# Fuzz-offboard.net
KiCad netlist of a schematic drawn in EAGLE
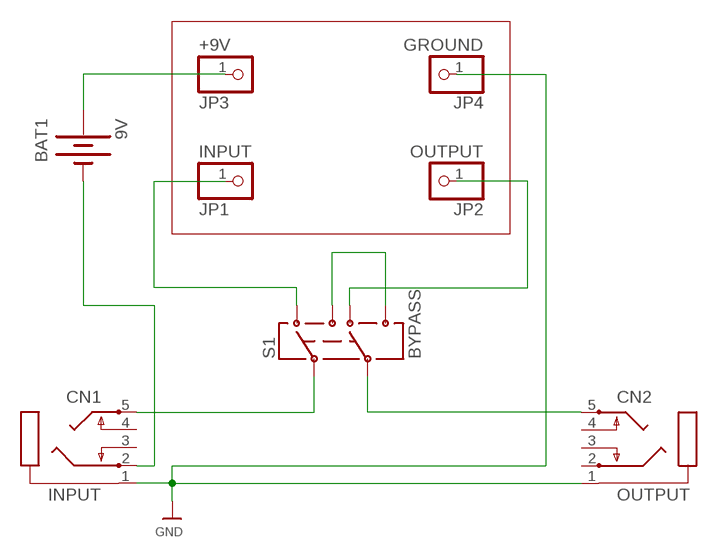
[diagram p0: schematic, sheet 1]

(export (version "E")
  (design (tool "Eeschema 10.0.6"))
  (components
    (comp (ref "BAT1")
      (value "9V")
      (footprint "eagle-import:BATTCON_9V")
      (libsource (lib "eagle-import") (part "BATTERY9V"))
    )
    (comp (ref "CN1")
      (value "INPUT")
      (footprint "eagle-import:STX3100")
      (libsource (lib "eagle-import") (part "AUDIO_STEREOJACK"))
    )
    (comp (ref "CN2")
      (value "OUTPUT")
      (footprint "eagle-import:STX3100")
      (libsource (lib "eagle-import") (part "AUDIO_STEREOJACK"))
    )
    (comp (ref "JP1")
      (value "INPUT")
      (footprint "eagle-import:1X01")
      (libsource (lib "eagle-import") (part "PINHD-1X1"))
    )
    (comp (ref "JP2")
      (value "OUTPUT")
      (footprint "eagle-import:1X01")
      (libsource (lib "eagle-import") (part "PINHD-1X1"))
    )
    (comp (ref "JP3")
      (value "+9V")
      (footprint "eagle-import:1X01")
      (libsource (lib "eagle-import") (part "PINHD-1X1"))
    )
    (comp (ref "JP4")
      (value "GROUND")
      (footprint "eagle-import:1X01")
      (libsource (lib "eagle-import") (part "PINHD-1X1"))
    )
    (comp (ref "S1")
      (value "BYPASS")
      (footprint "eagle-import:MS")
      (libsource (lib "eagle-import") (part "SWITCH-DPDTPTH1"))
    )
  )
  (nets
    (net (code "1") (name "GND") (class "Default")
      (node (ref "CN1") (pin "1") (pinfunction "1_1") (pintype "passive"))
      (node (ref "CN2") (pin "1") (pinfunction "1_1") (pintype "passive"))
      (node (ref "JP4") (pin "1") (pinfunction "1_1") (pintype "passive"))
    )
    (net (code "2") (name "Net-(BAT1-Pad+)") (class "Default")
      (node (ref "BAT1") (pin "+") (pinfunction "+_+") (pintype "power_in"))
      (node (ref "JP3") (pin "1") (pinfunction "1_1") (pintype "passive"))
    )
    (net (code "3") (name "Net-(BAT1-Pad-)") (class "Default")
      (node (ref "BAT1") (pin "-") (pinfunction "-_-") (pintype "power_in"))
      (node (ref "CN1") (pin "2") (pinfunction "2_2") (pintype "passive"))
    )
    (net (code "4") (name "Net-(CN1-Pad5)") (class "Default")
      (node (ref "CN1") (pin "5") (pinfunction "5_5") (pintype "passive"))
      (node (ref "S1") (pin "2") (pinfunction "2_2") (pintype "bidirectional"))
    )
    (net (code "5") (name "Net-(CN2-Pad5)") (class "Default")
      (node (ref "CN2") (pin "5") (pinfunction "5_5") (pintype "passive"))
      (node (ref "S1") (pin "5") (pinfunction "5_5") (pintype "bidirectional"))
    )
    (net (code "6") (name "Net-(JP1-Pad1)") (class "Default")
      (node (ref "JP1") (pin "1") (pinfunction "1_1") (pintype "passive"))
      (node (ref "S1") (pin "1") (pinfunction "1_1") (pintype "bidirectional"))
    )
    (net (code "7") (name "Net-(JP2-Pad1)") (class "Default")
      (node (ref "JP2") (pin "1") (pinfunction "1_1") (pintype "passive"))
      (node (ref "S1") (pin "4") (pinfunction "4_4") (pintype "bidirectional"))
    )
    (net (code "8") (name "Net-(S1-Pad3)") (class "Default")
      (node (ref "S1") (pin "3") (pinfunction "3_3") (pintype "bidirectional"))
      (node (ref "S1") (pin "6") (pinfunction "6_6") (pintype "bidirectional"))
    )
    (net (code "9") (name "unconnected-(CN1-Pad3)") (class "Default")
      (node (ref "CN1") (pin "3") (pinfunction "3_3") (pintype "passive"))
    )
    (net (code "10") (name "unconnected-(CN1-Pad4)") (class "Default")
      (node (ref "CN1") (pin "4") (pinfunction "4_4") (pintype "passive"))
    )
    (net (code "11") (name "unconnected-(CN2-Pad2)") (class "Default")
      (node (ref "CN2") (pin "2") (pinfunction "2_2") (pintype "passive"))
    )
    (net (code "12") (name "unconnected-(CN2-Pad3)") (class "Default")
      (node (ref "CN2") (pin "3") (pinfunction "3_3") (pintype "passive"))
    )
    (net (code "13") (name "unconnected-(CN2-Pad4)") (class "Default")
      (node (ref "CN2") (pin "4") (pinfunction "4_4") (pintype "passive"))
    )
  )
)
